# Rocketometer2148_MPU9150.net
KiCad netlist of a schematic drawn in EAGLE
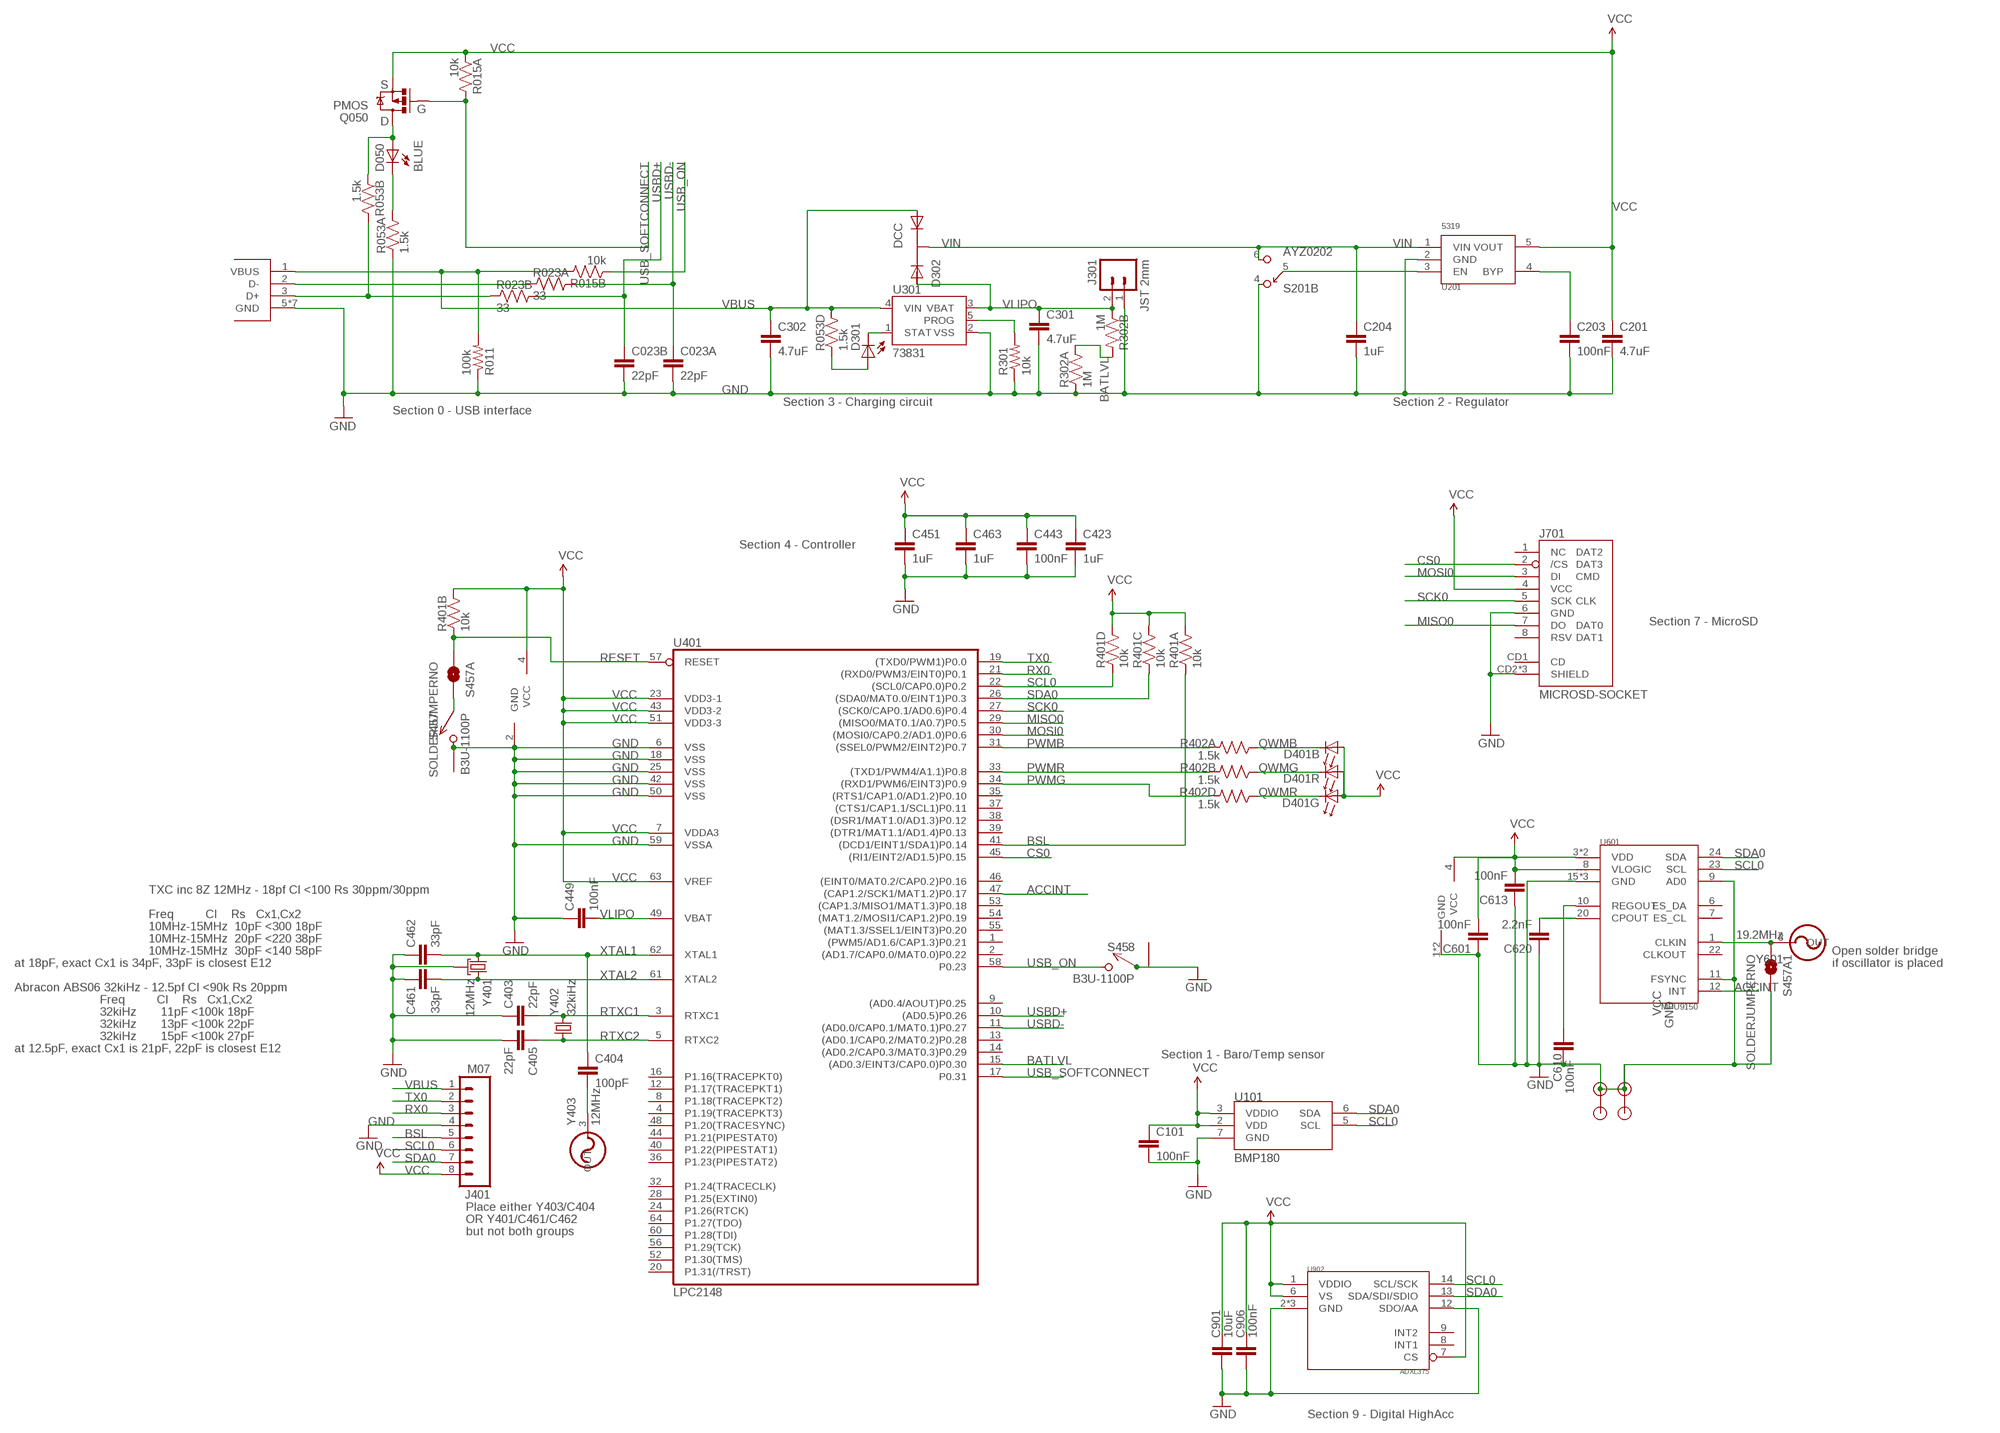
[diagram p0: schematic, sheet 1]

(export (version "E")
  (design (tool "Eeschema 10.0.6"))
  (components
    (comp (ref "C023")
      (value "22pF")
      (footprint "eagle-import:CKCM25")
      (fields (field (name "DIGIKEY") "445-1860-1-ND"))
      (libsource (lib "eagle-import") (part "CKCM25"))
    )
    (comp (ref "C101")
      (value "100nF")
      (footprint "eagle-import:0402-CAP")
      (libsource (lib "eagle-import") (part "CAP0402-CAP"))
    )
    (comp (ref "C201")
      (value "4.7uF")
      (footprint "eagle-import:0402-CAP")
      (libsource (lib "eagle-import") (part "CAP0402-CAP"))
    )
    (comp (ref "C203")
      (value "100nF")
      (footprint "eagle-import:0402-CAP")
      (libsource (lib "eagle-import") (part "CAP0402-CAP"))
    )
    (comp (ref "C204")
      (value "1uF")
      (footprint "eagle-import:0402-CAP")
      (libsource (lib "eagle-import") (part "CAP0402-CAP"))
    )
    (comp (ref "C301")
      (value "4.7uF")
      (footprint "eagle-import:0402-CAP")
      (libsource (lib "eagle-import") (part "CAP0402-CAP"))
    )
    (comp (ref "C302")
      (value "4.7uF")
      (footprint "eagle-import:0402-CAP")
      (libsource (lib "eagle-import") (part "CAP0402-CAP"))
    )
    (comp (ref "C403")
      (value "22pF")
      (footprint "eagle-import:0402-CAP")
      (libsource (lib "eagle-import") (part "CAP0402-CAP"))
    )
    (comp (ref "C404")
      (value "100pF")
      (footprint "eagle-import:0402-CAP")
      (libsource (lib "eagle-import") (part "CAP0402-CAP"))
    )
    (comp (ref "C405")
      (value "22pF")
      (footprint "eagle-import:0402-CAP")
      (libsource (lib "eagle-import") (part "CAP0402-CAP"))
    )
    (comp (ref "C423")
      (value "1uF")
      (footprint "eagle-import:0402-CAP")
      (libsource (lib "eagle-import") (part "CAP0402-CAP"))
    )
    (comp (ref "C443")
      (value "100nF")
      (footprint "eagle-import:0402-CAP")
      (libsource (lib "eagle-import") (part "CAP0402-CAP"))
    )
    (comp (ref "C449")
      (value "100nF")
      (footprint "eagle-import:0402-CAP")
      (libsource (lib "eagle-import") (part "CAP0402-CAP"))
    )
    (comp (ref "C451")
      (value "1uF")
      (footprint "eagle-import:0402-CAP")
      (libsource (lib "eagle-import") (part "CAP0402-CAP"))
    )
    (comp (ref "C461")
      (value "33pF")
      (footprint "eagle-import:0402-CAP")
      (libsource (lib "eagle-import") (part "CAP0402-CAP"))
    )
    (comp (ref "C462")
      (value "33pF")
      (footprint "eagle-import:0402-CAP")
      (libsource (lib "eagle-import") (part "CAP0402-CAP"))
    )
    (comp (ref "C463")
      (value "1uF")
      (footprint "eagle-import:0402-CAP")
      (libsource (lib "eagle-import") (part "CAP0402-CAP"))
    )
    (comp (ref "C601")
      (value "100nF")
      (footprint "eagle-import:0402-CAP")
      (libsource (lib "eagle-import") (part "CAP0402-CAP"))
    )
    (comp (ref "C610")
      (value "100nF")
      (footprint "eagle-import:0402-CAP")
      (libsource (lib "eagle-import") (part "CAP0402-CAP"))
    )
    (comp (ref "C613")
      (value "100nF")
      (footprint "eagle-import:0402-CAP")
      (libsource (lib "eagle-import") (part "CAP0402-CAP"))
    )
    (comp (ref "C620")
      (value "2.2nF")
      (footprint "eagle-import:0402-CAP")
      (libsource (lib "eagle-import") (part "CAP0402-CAP"))
    )
    (comp (ref "C901")
      (value "10uF")
      (footprint "eagle-import:0603-CAP")
      (libsource (lib "eagle-import") (part "CAP0603-CAP"))
    )
    (comp (ref "C906")
      (value "100nF")
      (footprint "eagle-import:0402-CAP")
      (libsource (lib "eagle-import") (part "SparkFun-Passives_CAP0402-CAP"))
    )
    (comp (ref "D050")
      (value "BLUE")
      (footprint "eagle-import:LED-0603")
      (libsource (lib "eagle-import") (part "LED0603"))
    )
    (comp (ref "D301")
      (value "YELLOW")
      (footprint "eagle-import:LED-0603")
      (libsource (lib "eagle-import") (part "LED0603"))
    )
    (comp (ref "D302")
      (value "DCC")
      (footprint "eagle-import:SOT-23-3")
      (libsource (lib "eagle-import") (part "PMEG2005CT"))
    )
    (comp (ref "D401")
      (value "SMLP36RGB2W(R)")
      (footprint "eagle-import:SMLP36")
      (fields (field (name "DIGIKEY") "846-1097-1-ND"))
      (libsource (lib "eagle-import") (part "SMLP36RGB2W(R)"))
    )
    (comp (ref "J001")
      (value "USB_MICROB_JSTGCT")
      (footprint "eagle-import:USB_MICROB_3075")
      (libsource (lib "eagle-import") (part "USB_MICROB_JSTGCT"))
    )
    (comp (ref "J301")
      (value "JST 2mm")
      (footprint "eagle-import:JST-2-SMD")
      (libsource (lib "eagle-import") (part "M02-JST-2MM-SMT"))
    )
    (comp (ref "J401")
      (value "M07")
      (footprint "eagle-import:1X08")
      (libsource (lib "eagle-import") (part "M081X08"))
    )
    (comp (ref "J701")
      (value "MICROSD-SOCKET")
      (footprint "eagle-import:MICROSD-SOCKET-PP")
      (libsource (lib "eagle-import") (part "MICROSD-SOCKET"))
    )
    (comp (ref "JP1")
      (value "STANDOFF")
      (footprint "eagle-import:STANDOFF")
      (libsource (lib "eagle-import") (part "STANDOFF"))
    )
    (comp (ref "JP2")
      (value "STANDOFF")
      (footprint "eagle-import:STANDOFF")
      (libsource (lib "eagle-import") (part "STANDOFF"))
    )
    (comp (ref "JP4")
      (value "STANDOFF")
      (footprint "eagle-import:STANDOFF")
      (libsource (lib "eagle-import") (part "STANDOFF"))
    )
    (comp (ref "JP5")
      (value "STANDOFF")
      (footprint "eagle-import:STANDOFF")
      (libsource (lib "eagle-import") (part "STANDOFF"))
    )
    (comp (ref "Q050")
      (value "PMOS")
      (footprint "eagle-import:SOT23-3")
      (libsource (lib "eagle-import") (part "MOSFET-PCHANNELSMD"))
    )
    (comp (ref "R011")
      (value "100k")
      (footprint "eagle-import:0402-RES")
      (libsource (lib "eagle-import") (part "RESISTOR0402-RES"))
    )
    (comp (ref "R015")
      (value "10k")
      (footprint "eagle-import:CRA02")
      (fields (field (name "DIGIKEY") "Y5103CT-ND"))
      (libsource (lib "eagle-import") (part "RP2EXB24V"))
    )
    (comp (ref "R023")
      (value "33")
      (footprint "eagle-import:CRA02")
      (libsource (lib "eagle-import") (part "RP2EXB24V"))
    )
    (comp (ref "R053")
      (value "1.5k")
      (footprint "eagle-import:CRA04")
      (fields (field (name "DIGIKEY") "CRA4S81.5KCT-ND"))
      (libsource (lib "eagle-import") (part "RP404"))
    )
    (comp (ref "R301")
      (value "10k")
      (footprint "eagle-import:0402-RES")
      (libsource (lib "eagle-import") (part "RESISTOR0402-RES"))
    )
    (comp (ref "R302")
      (value "1M")
      (footprint "eagle-import:CRA02")
      (libsource (lib "eagle-import") (part "RP2EXB24V"))
    )
    (comp (ref "R401")
      (value "10k")
      (footprint "eagle-import:CRA04")
      (fields (field (name "DIGIKEY") "CRA4S810KCT-ND"))
      (libsource (lib "eagle-import") (part "RP404"))
    )
    (comp (ref "R402")
      (value "1.5k")
      (footprint "eagle-import:CRA04")
      (fields (field (name "DIGIKEY") "CRA4S81.5KCT-ND"))
      (libsource (lib "eagle-import") (part "RP404"))
    )
    (comp (ref "S201")
      (value "AYZ0202")
      (footprint "eagle-import:AYZ0202")
      (libsource (lib "eagle-import") (part "AYZ0202"))
    )
    (comp (ref "S457")
      (value "B3U-1100P")
      (footprint "eagle-import:B3U-1100P")
      (fields (field (name "DIGIKEY") "SW1021CT-ND"))
      (libsource (lib "eagle-import") (part "B3U-1100P"))
    )
    (comp (ref "S457A")
      (value "SOLDERJUMPERNO")
      (footprint "eagle-import:SJ_2S-NO")
      (libsource (lib "eagle-import") (part "SOLDERJUMPERNO"))
    )
    (comp (ref "S457A1")
      (value "SOLDERJUMPERNO")
      (footprint "eagle-import:SJ_2S-NO")
      (libsource (lib "eagle-import") (part "SOLDERJUMPERNO"))
    )
    (comp (ref "S458")
      (value "B3U-1100P")
      (footprint "eagle-import:B3U-1100P")
      (fields (field (name "DIGIKEY") "SW1021CT-ND"))
      (libsource (lib "eagle-import") (part "B3U-1100P"))
    )
    (comp (ref "U101")
      (value "BMP180")
      (footprint "eagle-import:BMP180")
      (libsource (lib "eagle-import") (part "BMP180"))
    )
    (comp (ref "U201")
      (value "5319")
      (footprint "eagle-import:SOT-23-5")
      (libsource (lib "eagle-import") (part "MIC5319D5"))
    )
    (comp (ref "U301")
      (value "73831")
      (footprint "eagle-import:SOT23-5")
      (libsource (lib "eagle-import") (part "MCP73831"))
    )
    (comp (ref "U401")
      (value "LPC2148")
      (footprint "eagle-import:SQFP-S-10X10-64")
      (libsource (lib "eagle-import") (part "LPC213X"))
    )
    (comp (ref "U601")
      (value "MPU9150")
      (footprint "eagle-import:LLGA24")
      (libsource (lib "eagle-import") (part "MPU9150"))
    )
    (comp (ref "U902")
      (value "ADXL375")
      (footprint "eagle-import:ADXL375")
      (libsource (lib "eagle-import") (part "ADXL375"))
    )
    (comp (ref "Y401")
      (value "12MHz")
      (footprint "eagle-import:CRYSTAL_SMD_2MM_2_5MM")
      (libsource (lib "eagle-import") (part "CX2520"))
    )
    (comp (ref "Y402")
      (value "32kiHz")
      (footprint "eagle-import:ABS06")
      (libsource (lib "eagle-import") (part "ABS06"))
    )
    (comp (ref "Y403")
      (value "12MHz")
      (footprint "eagle-import:CRYSTAL_SMD_5MM_3_2MM")
      (fields (field (name "DIGIKEY") "631-1068-1-ND"))
      (libsource (lib "eagle-import") (part "OSCILLATORE35MT"))
    )
    (comp (ref "Y601")
      (value "19.2MHz")
      (footprint "eagle-import:CRYSTAL_SMD_2MM_2_5MM")
      (libsource (lib "eagle-import") (part "OSCILLATORASDMB"))
    )
  )
  (nets
    (net (code "1") (name "/ACCINT") (class "Default")
      (node (ref "U401") (pin "47") (pinfunction "(CAP1.2/SCK1/MAT1.2)P0.17_47") (pintype "bidirectional"))
      (node (ref "U601") (pin "12") (pinfunction "INT_12") (pintype "bidirectional"))
    )
    (net (code "2") (name "/BATLVL") (class "Default")
      (node (ref "R302") (pin "3") (pinfunction "2_3") (pintype "passive"))
      (node (ref "R302") (pin "4") (pinfunction "2_4") (pintype "passive"))
      (node (ref "U401") (pin "15") (pinfunction "(AD0.3/EINT3/CAP0.0)P0.30_15") (pintype "bidirectional"))
    )
    (net (code "3") (name "/BSL") (class "Default")
      (node (ref "J401") (pin "5") (pinfunction "5_5") (pintype "passive"))
      (node (ref "R401") (pin "1") (pinfunction "1_1") (pintype "passive"))
      (node (ref "U401") (pin "41") (pinfunction "(DCD1/EINT1/SDA1)P0.14_41") (pintype "bidirectional"))
    )
    (net (code "4") (name "/CS0") (class "Default")
      (node (ref "J701") (pin "2") (pinfunction "/CS_2") (pintype "bidirectional"))
      (node (ref "U401") (pin "45") (pinfunction "(RI1/EINT2/AD1.5)P0.15_45") (pintype "bidirectional"))
    )
    (net (code "5") (name "/MISO0") (class "Default")
      (node (ref "J701") (pin "7") (pinfunction "DO_7") (pintype "bidirectional"))
      (node (ref "U401") (pin "29") (pinfunction "(MISO0/MAT0.1/A0.7)P0.5_29") (pintype "bidirectional"))
    )
    (net (code "6") (name "/MOSI0") (class "Default")
      (node (ref "J701") (pin "3") (pinfunction "DI_3") (pintype "bidirectional"))
      (node (ref "U401") (pin "30") (pinfunction "(MOSI0/CAP0.2/AD1.0)P0.6_30") (pintype "bidirectional"))
    )
    (net (code "7") (name "/PWMB") (class "Default")
      (node (ref "R402") (pin "8") (pinfunction "2_8") (pintype "passive"))
      (node (ref "U401") (pin "31") (pinfunction "(SSEL0/PWM2/EINT2)P0.7_31") (pintype "bidirectional"))
    )
    (net (code "8") (name "/PWMG") (class "Default")
      (node (ref "R402") (pin "5") (pinfunction "2_5") (pintype "passive"))
      (node (ref "U401") (pin "34") (pinfunction "(RXD1/PWM6/EINT3)P0.9_34") (pintype "bidirectional"))
    )
    (net (code "9") (name "/PWMR") (class "Default")
      (node (ref "R402") (pin "7") (pinfunction "2_7") (pintype "passive"))
      (node (ref "U401") (pin "33") (pinfunction "(TXD1/PWM4/A1.1)P0.8_33") (pintype "bidirectional"))
    )
    (net (code "10") (name "/QWMB") (class "Default")
      (node (ref "D401") (pin "1") (pinfunction "C_1") (pintype "passive"))
      (node (ref "R402") (pin "1") (pinfunction "1_1") (pintype "passive"))
    )
    (net (code "11") (name "/QWMG") (class "Default")
      (node (ref "D401") (pin "5") (pinfunction "C_5") (pintype "passive"))
      (node (ref "R402") (pin "4") (pinfunction "1_4") (pintype "passive"))
    )
    (net (code "12") (name "/QWMR") (class "Default")
      (node (ref "D401") (pin "3") (pinfunction "C_3") (pintype "passive"))
      (node (ref "R402") (pin "2") (pinfunction "1_2") (pintype "passive"))
    )
    (net (code "13") (name "/RESET") (class "Default")
      (node (ref "R401") (pin "2") (pinfunction "1_2") (pintype "passive"))
      (node (ref "S457A") (pin "1") (pinfunction "1_1") (pintype "passive"))
      (node (ref "U401") (pin "57") (pinfunction "RESET_57") (pintype "input"))
    )
    (net (code "14") (name "/RTXC1") (class "Default")
      (node (ref "C403") (pin "2") (pinfunction "2_2") (pintype "passive"))
      (node (ref "U401") (pin "3") (pinfunction "RTXC1_3") (pintype "input"))
      (node (ref "Y402") (pin "2") (pinfunction "2_2") (pintype "passive"))
    )
    (net (code "15") (name "/RTXC2") (class "Default")
      (node (ref "C405") (pin "1") (pinfunction "1_1") (pintype "passive"))
      (node (ref "U401") (pin "5") (pinfunction "RTXC2_5") (pintype "output"))
      (node (ref "Y402") (pin "1") (pinfunction "1_1") (pintype "passive"))
    )
    (net (code "16") (name "/RX0") (class "Default")
      (node (ref "J401") (pin "3") (pinfunction "3_3") (pintype "passive"))
      (node (ref "U401") (pin "21") (pinfunction "(RXD0/PWM3/EINT0)P0.1_21") (pintype "bidirectional"))
    )
    (net (code "17") (name "/SCK0") (class "Default")
      (node (ref "J701") (pin "5") (pinfunction "SCK_5") (pintype "bidirectional"))
      (node (ref "U401") (pin "27") (pinfunction "(SCK0/CAP0.1/AD0.6)P0.4_27") (pintype "bidirectional"))
    )
    (net (code "18") (name "/SCL0") (class "Default")
      (node (ref "J401") (pin "6") (pinfunction "6_6") (pintype "passive"))
      (node (ref "R401") (pin "4") (pinfunction "1_4") (pintype "passive"))
      (node (ref "U101") (pin "5") (pinfunction "SCL_5") (pintype "input"))
      (node (ref "U401") (pin "22") (pinfunction "(SCL0/CAP0.0)P0.2_22") (pintype "bidirectional"))
      (node (ref "U601") (pin "23") (pinfunction "SCL_23") (pintype "bidirectional"))
      (node (ref "U902") (pin "14") (pinfunction "SCL/SCK_14") (pintype "input"))
    )
    (net (code "19") (name "/SDA0") (class "Default")
      (node (ref "J401") (pin "7") (pinfunction "7_7") (pintype "passive"))
      (node (ref "R401") (pin "3") (pinfunction "1_3") (pintype "passive"))
      (node (ref "U101") (pin "6") (pinfunction "SDA_6") (pintype "bidirectional"))
      (node (ref "U401") (pin "26") (pinfunction "(SDA0/MAT0.0/EINT1)P0.3_26") (pintype "bidirectional"))
      (node (ref "U601") (pin "24") (pinfunction "SDA_24") (pintype "bidirectional"))
      (node (ref "U902") (pin "13") (pinfunction "SDA/SDI/SDIO_13") (pintype "bidirectional"))
    )
    (net (code "20") (name "/TX0") (class "Default")
      (node (ref "J401") (pin "2") (pinfunction "2_2") (pintype "passive"))
      (node (ref "U401") (pin "19") (pinfunction "(TXD0/PWM1)P0.0_19") (pintype "bidirectional"))
    )
    (net (code "21") (name "/USBD+") (class "Default")
      (node (ref "C023") (pin "2") (pinfunction "1_2") (pintype "passive"))
      (node (ref "R023") (pin "3") (pinfunction "2_3") (pintype "passive"))
      (node (ref "U401") (pin "10") (pinfunction "(AD0.5)P0.26_10") (pintype "bidirectional"))
    )
    (net (code "22") (name "/USBD-") (class "Default")
      (node (ref "C023") (pin "1") (pinfunction "1_1") (pintype "passive"))
      (node (ref "R023") (pin "4") (pinfunction "2_4") (pintype "passive"))
      (node (ref "U401") (pin "11") (pinfunction "(AD0.0/CAP0.1/MAT0.1)P0.27_11") (pintype "bidirectional"))
    )
    (net (code "23") (name "/USB_ON") (class "Default")
      (node (ref "R015") (pin "2") (pinfunction "1_2") (pintype "passive"))
      (node (ref "S458") (pin "P$2") (pinfunction "2_P$2") (pintype "bidirectional"))
      (node (ref "U401") (pin "58") (pinfunction "P0.23_58") (pintype "bidirectional"))
    )
    (net (code "24") (name "/USB_SOFTCONNECT") (class "Default")
      (node (ref "Q050") (pin "1") (pinfunction "G_1") (pintype "passive"))
      (node (ref "R015") (pin "4") (pinfunction "2_4") (pintype "passive"))
      (node (ref "U401") (pin "17") (pinfunction "P0.31_17") (pintype "output"))
    )
    (net (code "25") (name "/VBUS") (class "Default")
      (node (ref "C302") (pin "1") (pinfunction "1_1") (pintype "passive"))
      (node (ref "D302") (pin "1") (pinfunction "A1_1") (pintype "passive"))
      (node (ref "J001") (pin "1") (pinfunction "VBUS_1") (pintype "bidirectional"))
      (node (ref "J401") (pin "1") (pinfunction "1_1") (pintype "passive"))
      (node (ref "R011") (pin "2") (pinfunction "2_2") (pintype "passive"))
      (node (ref "R015") (pin "3") (pinfunction "2_3") (pintype "passive"))
      (node (ref "R053") (pin "5") (pinfunction "2_5") (pintype "passive"))
      (node (ref "U301") (pin "4") (pinfunction "VIN_4") (pintype "power_in"))
    )
    (net (code "26") (name "/VIN") (class "Default")
      (node (ref "C204") (pin "1") (pinfunction "1_1") (pintype "passive"))
      (node (ref "D302") (pin "3") (pinfunction "K_3") (pintype "passive"))
      (node (ref "S201") (pin "6") (pinfunction "P$2_6") (pintype "bidirectional"))
      (node (ref "U201") (pin "1") (pinfunction "VIN_1") (pintype "bidirectional"))
    )
    (net (code "27") (name "/VLIPO") (class "Default")
      (node (ref "C301") (pin "1") (pinfunction "1_1") (pintype "passive"))
      (node (ref "C449") (pin "2") (pinfunction "2_2") (pintype "passive"))
      (node (ref "D302") (pin "2") (pinfunction "A2_2") (pintype "passive"))
      (node (ref "J301") (pin "2") (pinfunction "2_2") (pintype "passive"))
      (node (ref "R302") (pin "2") (pinfunction "1_2") (pintype "passive"))
      (node (ref "U301") (pin "3") (pinfunction "VBAT_3") (pintype "power_in"))
      (node (ref "U401") (pin "49") (pinfunction "VBAT_49") (pintype "power_in"))
    )
    (net (code "28") (name "/XTAL1") (class "Default")
      (node (ref "C404") (pin "1") (pinfunction "1_1") (pintype "passive"))
      (node (ref "C462") (pin "2") (pinfunction "2_2") (pintype "passive"))
      (node (ref "U401") (pin "62") (pinfunction "XTAL1_62") (pintype "input"))
      (node (ref "Y401") (pin "1") (pinfunction "1_1") (pintype "passive"))
    )
    (net (code "29") (name "/XTAL2") (class "Default")
      (node (ref "C461") (pin "2") (pinfunction "2_2") (pintype "passive"))
      (node (ref "U401") (pin "61") (pinfunction "XTAL2_61") (pintype "output"))
      (node (ref "Y401") (pin "3") (pinfunction "2_3") (pintype "passive"))
    )
    (net (code "30") (name "GND") (class "Default")
      (node (ref "C023") (pin "3") (pinfunction "2_3") (pintype "passive"))
      (node (ref "C023") (pin "4") (pinfunction "2_4") (pintype "passive"))
      (node (ref "C101") (pin "2") (pinfunction "2_2") (pintype "passive"))
      (node (ref "C201") (pin "2") (pinfunction "2_2") (pintype "passive"))
      (node (ref "C203") (pin "2") (pinfunction "2_2") (pintype "passive"))
      (node (ref "C204") (pin "2") (pinfunction "2_2") (pintype "passive"))
      (node (ref "C301") (pin "2") (pinfunction "2_2") (pintype "passive"))
      (node (ref "C302") (pin "2") (pinfunction "2_2") (pintype "passive"))
      (node (ref "C403") (pin "1") (pinfunction "1_1") (pintype "passive"))
      (node (ref "C405") (pin "2") (pinfunction "2_2") (pintype "passive"))
      (node (ref "C423") (pin "2") (pinfunction "2_2") (pintype "passive"))
      (node (ref "C443") (pin "2") (pinfunction "2_2") (pintype "passive"))
      (node (ref "C449") (pin "1") (pinfunction "1_1") (pintype "passive"))
      (node (ref "C451") (pin "2") (pinfunction "2_2") (pintype "passive"))
      (node (ref "C461") (pin "1") (pinfunction "1_1") (pintype "passive"))
      (node (ref "C462") (pin "1") (pinfunction "1_1") (pintype "passive"))
      (node (ref "C463") (pin "2") (pinfunction "2_2") (pintype "passive"))
      (node (ref "C601") (pin "1") (pinfunction "1_1") (pintype "passive"))
      (node (ref "C610") (pin "2") (pinfunction "2_2") (pintype "passive"))
      (node (ref "C613") (pin "1") (pinfunction "1_1") (pintype "passive"))
      (node (ref "C620") (pin "1") (pinfunction "1_1") (pintype "passive"))
      (node (ref "C901") (pin "2") (pinfunction "2_2") (pintype "passive"))
      (node (ref "C906") (pin "2") (pinfunction "2_2") (pintype "passive"))
      (node (ref "J001") (pin "5") (pinfunction "GND_5") (pintype "bidirectional"))
      (node (ref "J001") (pin "P$1") (pinfunction "GND_P$1") (pintype "bidirectional"))
      (node (ref "J001") (pin "P$10") (pinfunction "GND_P$10") (pintype "bidirectional"))
      (node (ref "J001") (pin "P$2") (pinfunction "GND_P$2") (pintype "bidirectional"))
      (node (ref "J001") (pin "P$3") (pinfunction "GND_P$3") (pintype "bidirectional"))
      (node (ref "J001") (pin "P$4") (pinfunction "GND_P$4") (pintype "bidirectional"))
      (node (ref "J001") (pin "P$8") (pinfunction "GND_P$8") (pintype "bidirectional"))
      (node (ref "J301") (pin "1") (pinfunction "1_1") (pintype "passive"))
      (node (ref "J401") (pin "4") (pinfunction "4_4") (pintype "passive"))
      (node (ref "J701") (pin "6") (pinfunction "GND_6") (pintype "bidirectional"))
      (node (ref "J701") (pin "CD2") (pinfunction "SHIELD_CD2") (pintype "bidirectional"))
      (node (ref "J701") (pin "GND1") (pinfunction "SHIELD_GND1") (pintype "bidirectional"))
      (node (ref "J701") (pin "GND3") (pinfunction "SHIELD_GND3") (pintype "bidirectional"))
      (node (ref "JP1") (pin "P$1") (pinfunction "P$1_P$1") (pintype "bidirectional"))
      (node (ref "JP2") (pin "P$1") (pinfunction "P$1_P$1") (pintype "bidirectional"))
      (node (ref "JP4") (pin "P$1") (pinfunction "P$1_P$1") (pintype "bidirectional"))
      (node (ref "JP5") (pin "P$1") (pinfunction "P$1_P$1") (pintype "bidirectional"))
      (node (ref "R011") (pin "1") (pinfunction "1_1") (pintype "passive"))
      (node (ref "R053") (pin "1") (pinfunction "1_1") (pintype "passive"))
      (node (ref "R301") (pin "1") (pinfunction "1_1") (pintype "passive"))
      (node (ref "R302") (pin "1") (pinfunction "1_1") (pintype "passive"))
      (node (ref "S201") (pin "4") (pinfunction "P$1_4") (pintype "bidirectional"))
      (node (ref "S457") (pin "P$2") (pinfunction "2_P$2") (pintype "bidirectional"))
      (node (ref "S457") (pin "P$3") (pinfunction "1_P$3") (pintype "bidirectional"))
      (node (ref "S457A1") (pin "2") (pinfunction "2_2") (pintype "passive"))
      (node (ref "S458") (pin "P$1") (pinfunction "1_P$1") (pintype "bidirectional"))
      (node (ref "S458") (pin "P$3") (pinfunction "1_P$3") (pintype "bidirectional"))
      (node (ref "U101") (pin "7") (pinfunction "GND_7") (pintype "power_in"))
      (node (ref "U201") (pin "2") (pinfunction "GND_2") (pintype "bidirectional"))
      (node (ref "U301") (pin "2") (pinfunction "VSS_2") (pintype "power_in"))
      (node (ref "U401") (pin "18") (pinfunction "VSS_18") (pintype "power_in"))
      (node (ref "U401") (pin "25") (pinfunction "VSS_25") (pintype "power_in"))
      (node (ref "U401") (pin "42") (pinfunction "VSS_42") (pintype "power_in"))
      (node (ref "U401") (pin "50") (pinfunction "VSS_50") (pintype "power_in"))
      (node (ref "U401") (pin "59") (pinfunction "VSSA_59") (pintype "power_in"))
      (node (ref "U401") (pin "6") (pinfunction "VSS_6") (pintype "power_in"))
      (node (ref "U601") (pin "11") (pinfunction "FSYNC_11") (pintype "bidirectional"))
      (node (ref "U601") (pin "15") (pinfunction "GND_15") (pintype "bidirectional"))
      (node (ref "U601") (pin "17") (pinfunction "GND_17") (pintype "bidirectional"))
      (node (ref "U601") (pin "18") (pinfunction "GND_18") (pintype "bidirectional"))
      (node (ref "U601") (pin "9") (pinfunction "AD0_9") (pintype "bidirectional"))
      (node (ref "U902") (pin "12") (pinfunction "SDO/AA_12") (pintype "bidirectional"))
      (node (ref "U902") (pin "2") (pinfunction "GND_2") (pintype "power_in"))
      (node (ref "U902") (pin "4") (pinfunction "GND_4") (pintype "power_in"))
      (node (ref "U902") (pin "5") (pinfunction "GND_5") (pintype "power_in"))
      (node (ref "Y401") (pin "2") (pinfunction "GND_2") (pintype "passive"))
      (node (ref "Y401") (pin "4") (pinfunction "GND_4") (pintype "passive"))
      (node (ref "Y403") (pin "2") (pinfunction "GND_2") (pintype "bidirectional"))
      (node (ref "Y601") (pin "1") (pinfunction "GND_1") (pintype "bidirectional"))
      (node (ref "Y601") (pin "2") (pinfunction "GND_2") (pintype "bidirectional"))
    )
    (net (code "31") (name "Net-(J001-D+)") (class "Default")
      (node (ref "J001") (pin "3") (pinfunction "D+_3") (pintype "bidirectional"))
      (node (ref "R023") (pin "2") (pinfunction "1_2") (pintype "passive"))
      (node (ref "R053") (pin "7") (pinfunction "2_7") (pintype "passive"))
    )
    (net (code "32") (name "Net-(J001-D-)") (class "Default")
      (node (ref "J001") (pin "2") (pinfunction "D-_2") (pintype "bidirectional"))
      (node (ref "R023") (pin "1") (pinfunction "1_1") (pintype "passive"))
    )
    (net (code "33") (name "Net-(Q050-D)") (class "Default")
      (node (ref "D050") (pin "A") (pinfunction "A_A") (pintype "passive"))
      (node (ref "Q050") (pin "3") (pinfunction "D_3") (pintype "passive"))
      (node (ref "R053") (pin "2") (pinfunction "1_2") (pintype "passive"))
    )
    (net (code "34") (name "Net-(R053A-2)") (class "Default")
      (node (ref "D050") (pin "C") (pinfunction "C_C") (pintype "passive"))
      (node (ref "R053") (pin "8") (pinfunction "2_8") (pintype "passive"))
    )
    (net (code "35") (name "Net-(R053D-1)") (class "Default")
      (node (ref "D301") (pin "A") (pinfunction "A_A") (pintype "passive"))
      (node (ref "R053") (pin "4") (pinfunction "1_4") (pintype "passive"))
    )
    (net (code "36") (name "Net-(S201B-P$3)") (class "Default")
      (node (ref "S201") (pin "5") (pinfunction "P$3_5") (pintype "bidirectional"))
      (node (ref "U201") (pin "3") (pinfunction "EN_3") (pintype "bidirectional"))
    )
    (net (code "37") (name "Net-(S457B-1)") (class "Default")
      (node (ref "S457") (pin "P$1") (pinfunction "1_P$1") (pintype "bidirectional"))
      (node (ref "S457A") (pin "2") (pinfunction "2_2") (pintype "passive"))
    )
    (net (code "38") (name "Net-(U201-BYP)") (class "Default")
      (node (ref "C203") (pin "1") (pinfunction "1_1") (pintype "passive"))
      (node (ref "U201") (pin "4") (pinfunction "BYP_4") (pintype "bidirectional"))
    )
    (net (code "39") (name "Net-(U301-PROG)") (class "Default")
      (node (ref "R301") (pin "2") (pinfunction "2_2") (pintype "passive"))
      (node (ref "U301") (pin "5") (pinfunction "PROG_5") (pintype "input"))
    )
    (net (code "40") (name "Net-(U301-STAT)") (class "Default")
      (node (ref "D301") (pin "C") (pinfunction "C_C") (pintype "passive"))
      (node (ref "U301") (pin "1") (pinfunction "STAT_1") (pintype "output"))
    )
    (net (code "41") (name "Net-(U601-CLKIN)") (class "Default")
      (node (ref "S457A1") (pin "1") (pinfunction "1_1") (pintype "passive"))
      (node (ref "U601") (pin "1") (pinfunction "CLKIN_1") (pintype "bidirectional"))
      (node (ref "Y601") (pin "3") (pinfunction "OUT_3") (pintype "bidirectional"))
    )
    (net (code "42") (name "Net-(U601-CPOUT)") (class "Default")
      (node (ref "C620") (pin "2") (pinfunction "2_2") (pintype "passive"))
      (node (ref "U601") (pin "20") (pinfunction "CPOUT_20") (pintype "bidirectional"))
    )
    (net (code "43") (name "Net-(U601-REGOUT)") (class "Default")
      (node (ref "C610") (pin "1") (pinfunction "1_1") (pintype "passive"))
      (node (ref "U601") (pin "10") (pinfunction "REGOUT_10") (pintype "bidirectional"))
    )
    (net (code "44") (name "Net-(Y403A-OUT)") (class "Default")
      (node (ref "C404") (pin "2") (pinfunction "2_2") (pintype "passive"))
      (node (ref "Y403") (pin "3") (pinfunction "OUT_3") (pintype "bidirectional"))
    )
    (net (code "45") (name "VCC") (class "Default")
      (node (ref "C101") (pin "1") (pinfunction "1_1") (pintype "passive"))
      (node (ref "C201") (pin "1") (pinfunction "1_1") (pintype "passive"))
      (node (ref "C423") (pin "1") (pinfunction "1_1") (pintype "passive"))
      (node (ref "C443") (pin "1") (pinfunction "1_1") (pintype "passive"))
      (node (ref "C451") (pin "1") (pinfunction "1_1") (pintype "passive"))
      (node (ref "C463") (pin "1") (pinfunction "1_1") (pintype "passive"))
      (node (ref "C601") (pin "2") (pinfunction "2_2") (pintype "passive"))
      (node (ref "C613") (pin "2") (pinfunction "2_2") (pintype "passive"))
      (node (ref "C901") (pin "1") (pinfunction "1_1") (pintype "passive"))
      (node (ref "C906") (pin "1") (pinfunction "1_1") (pintype "passive"))
      (node (ref "D401") (pin "2") (pinfunction "A_2") (pintype "passive"))
      (node (ref "D401") (pin "4") (pinfunction "A_4") (pintype "passive"))
      (node (ref "D401") (pin "6") (pinfunction "A_6") (pintype "passive"))
      (node (ref "J401") (pin "8") (pinfunction "8_8") (pintype "passive"))
      (node (ref "J701") (pin "4") (pinfunction "VCC_4") (pintype "bidirectional"))
      (node (ref "Q050") (pin "2") (pinfunction "S_2") (pintype "passive"))
      (node (ref "R015") (pin "1") (pinfunction "1_1") (pintype "passive"))
      (node (ref "R401") (pin "5") (pinfunction "2_5") (pintype "passive"))
      (node (ref "R401") (pin "6") (pinfunction "2_6") (pintype "passive"))
      (node (ref "R401") (pin "7") (pinfunction "2_7") (pintype "passive"))
      (node (ref "R401") (pin "8") (pinfunction "2_8") (pintype "passive"))
      (node (ref "U101") (pin "2") (pinfunction "VDD_2") (pintype "power_in"))
      (node (ref "U101") (pin "3") (pinfunction "VDDIO_3") (pintype "power_in"))
      (node (ref "U201") (pin "5") (pinfunction "VOUT_5") (pintype "bidirectional"))
      (node (ref "U401") (pin "23") (pinfunction "VDD3-1_23") (pintype "power_in"))
      (node (ref "U401") (pin "43") (pinfunction "VDD3-2_43") (pintype "power_in"))
      (node (ref "U401") (pin "51") (pinfunction "VDD3-3_51") (pintype "power_in"))
      (node (ref "U401") (pin "63") (pinfunction "VREF_63") (pintype "input"))
      (node (ref "U401") (pin "7") (pinfunction "VDDA3_7") (pintype "power_in"))
      (node (ref "U601") (pin "13") (pinfunction "VDD_13") (pintype "bidirectional"))
      (node (ref "U601") (pin "3") (pinfunction "VDD_3") (pintype "bidirectional"))
      (node (ref "U601") (pin "8") (pinfunction "VLOGIC_8") (pintype "bidirectional"))
      (node (ref "U902") (pin "1") (pinfunction "VDDIO_1") (pintype "power_in"))
      (node (ref "U902") (pin "6") (pinfunction "VS_6") (pintype "power_in"))
      (node (ref "U902") (pin "7") (pinfunction "CS_7") (pintype "input"))
      (node (ref "Y403") (pin "4") (pinfunction "VCC_4") (pintype "bidirectional"))
      (node (ref "Y601") (pin "4") (pinfunction "VCC_4") (pintype "bidirectional"))
    )
    (net (code "46") (name "unconnected-(J701-CD-PadCD1)") (class "Default")
      (node (ref "J701") (pin "CD1") (pinfunction "CD_CD1") (pintype "bidirectional"))
    )
    (net (code "47") (name "unconnected-(J701-NC-Pad1)") (class "Default")
      (node (ref "J701") (pin "1") (pinfunction "NC_1") (pintype "bidirectional"))
    )
    (net (code "48") (name "unconnected-(J701-RSV-Pad8)") (class "Default")
      (node (ref "J701") (pin "8") (pinfunction "RSV_8") (pintype "bidirectional"))
    )
    (net (code "49") (name "unconnected-(U401-(AD0.1{slash}CAP0.2{slash}MAT0.2)P0.28-Pad13)") (class "Default")
      (node (ref "U401") (pin "13") (pinfunction "(AD0.1/CAP0.2/MAT0.2)P0.28_13") (pintype "bidirectional"))
    )
    (net (code "50") (name "unconnected-(U401-(AD0.2{slash}CAP0.3{slash}MAT0.3)P0.29-Pad14)") (class "Default")
      (node (ref "U401") (pin "14") (pinfunction "(AD0.2/CAP0.3/MAT0.3)P0.29_14") (pintype "bidirectional"))
    )
    (net (code "51") (name "unconnected-(U401-(AD0.4{slash}AOUT)P0.25-Pad9)") (class "Default")
      (node (ref "U401") (pin "9") (pinfunction "(AD0.4/AOUT)P0.25_9") (pintype "bidirectional"))
    )
    (net (code "52") (name "unconnected-(U401-(AD1.7{slash}CAP0.0{slash}MAT0.0)P0.22-Pad2)") (class "Default")
      (node (ref "U401") (pin "2") (pinfunction "(AD1.7/CAP0.0/MAT0.0)P0.22_2") (pintype "bidirectional"))
    )
    (net (code "53") (name "unconnected-(U401-(CAP1.3{slash}MISO1{slash}MAT1.3)P0.18-Pad53)") (class "Default")
      (node (ref "U401") (pin "53") (pinfunction "(CAP1.3/MISO1/MAT1.3)P0.18_53") (pintype "bidirectional"))
    )
    (net (code "54") (name "unconnected-(U401-(CTS1{slash}CAP1.1{slash}SCL1)P0.11-Pad37)") (class "Default")
      (node (ref "U401") (pin "37") (pinfunction "(CTS1/CAP1.1/SCL1)P0.11_37") (pintype "bidirectional"))
    )
    (net (code "55") (name "unconnected-(U401-(DSR1{slash}MAT1.0{slash}AD1.3)P0.12-Pad38)") (class "Default")
      (node (ref "U401") (pin "38") (pinfunction "(DSR1/MAT1.0/AD1.3)P0.12_38") (pintype "bidirectional"))
    )
    (net (code "56") (name "unconnected-(U401-(DTR1{slash}MAT1.1{slash}AD1.4)P0.13-Pad39)") (class "Default")
      (node (ref "U401") (pin "39") (pinfunction "(DTR1/MAT1.1/AD1.4)P0.13_39") (pintype "bidirectional"))
    )
    (net (code "57") (name "unconnected-(U401-(EINT0{slash}MAT0.2{slash}CAP0.2)P0.16-Pad46)") (class "Default")
      (node (ref "U401") (pin "46") (pinfunction "(EINT0/MAT0.2/CAP0.2)P0.16_46") (pintype "bidirectional"))
    )
    (net (code "58") (name "unconnected-(U401-(MAT1.2{slash}MOSI1{slash}CAP1.2)P0.19-Pad54)") (class "Default")
      (node (ref "U401") (pin "54") (pinfunction "(MAT1.2/MOSI1/CAP1.2)P0.19_54") (pintype "bidirectional"))
    )
    (net (code "59") (name "unconnected-(U401-(MAT1.3{slash}SSEL1{slash}EINT3)P0.20-Pad55)") (class "Default")
      (node (ref "U401") (pin "55") (pinfunction "(MAT1.3/SSEL1/EINT3)P0.20_55") (pintype "bidirectional"))
    )
    (net (code "60") (name "unconnected-(U401-(PWM5{slash}AD1.6{slash}CAP1.3)P0.21-Pad1)") (class "Default")
      (node (ref "U401") (pin "1") (pinfunction "(PWM5/AD1.6/CAP1.3)P0.21_1") (pintype "bidirectional"))
    )
    (net (code "61") (name "unconnected-(U401-(RTS1{slash}CAP1.0{slash}AD1.2)P0.10-Pad35)") (class "Default")
      (node (ref "U401") (pin "35") (pinfunction "(RTS1/CAP1.0/AD1.2)P0.10_35") (pintype "bidirectional"))
    )
    (net (code "62") (name "unconnected-(U401-P1.16(TRACEPKT0)-Pad16)") (class "Default")
      (node (ref "U401") (pin "16") (pinfunction "P1.16(TRACEPKT0)_16") (pintype "bidirectional"))
    )
    (net (code "63") (name "unconnected-(U401-P1.17(TRACEPKT1)-Pad12)") (class "Default")
      (node (ref "U401") (pin "12") (pinfunction "P1.17(TRACEPKT1)_12") (pintype "bidirectional"))
    )
    (net (code "64") (name "unconnected-(U401-P1.18(TRACEPKT2)-Pad8)") (class "Default")
      (node (ref "U401") (pin "8") (pinfunction "P1.18(TRACEPKT2)_8") (pintype "bidirectional"))
    )
    (net (code "65") (name "unconnected-(U401-P1.19(TRACEPKT3)-Pad4)") (class "Default")
      (node (ref "U401") (pin "4") (pinfunction "P1.19(TRACEPKT3)_4") (pintype "bidirectional"))
    )
    (net (code "66") (name "unconnected-(U401-P1.20(TRACESYNC)-Pad48)") (class "Default")
      (node (ref "U401") (pin "48") (pinfunction "P1.20(TRACESYNC)_48") (pintype "bidirectional"))
    )
    (net (code "67") (name "unconnected-(U401-P1.21(PIPESTAT0)-Pad44)") (class "Default")
      (node (ref "U401") (pin "44") (pinfunction "P1.21(PIPESTAT0)_44") (pintype "bidirectional"))
    )
    (net (code "68") (name "unconnected-(U401-P1.22(PIPESTAT1)-Pad40)") (class "Default")
      (node (ref "U401") (pin "40") (pinfunction "P1.22(PIPESTAT1)_40") (pintype "bidirectional"))
    )
    (net (code "69") (name "unconnected-(U401-P1.23(PIPESTAT2)-Pad36)") (class "Default")
      (node (ref "U401") (pin "36") (pinfunction "P1.23(PIPESTAT2)_36") (pintype "bidirectional"))
    )
    (net (code "70") (name "unconnected-(U401-P1.24(TRACECLK)-Pad32)") (class "Default")
      (node (ref "U401") (pin "32") (pinfunction "P1.24(TRACECLK)_32") (pintype "bidirectional"))
    )
    (net (code "71") (name "unconnected-(U401-P1.25(EXTIN0)-Pad28)") (class "Default")
      (node (ref "U401") (pin "28") (pinfunction "P1.25(EXTIN0)_28") (pintype "bidirectional"))
    )
    (net (code "72") (name "unconnected-(U401-P1.26(RTCK)-Pad24)") (class "Default")
      (node (ref "U401") (pin "24") (pinfunction "P1.26(RTCK)_24") (pintype "bidirectional"))
    )
    (net (code "73") (name "unconnected-(U401-P1.27(TDO)-Pad64)") (class "Default")
      (node (ref "U401") (pin "64") (pinfunction "P1.27(TDO)_64") (pintype "bidirectional"))
    )
    (net (code "74") (name "unconnected-(U401-P1.28(TDI)-Pad60)") (class "Default")
      (node (ref "U401") (pin "60") (pinfunction "P1.28(TDI)_60") (pintype "bidirectional"))
    )
    (net (code "75") (name "unconnected-(U401-P1.29(TCK)-Pad56)") (class "Default")
      (node (ref "U401") (pin "56") (pinfunction "P1.29(TCK)_56") (pintype "bidirectional"))
    )
    (net (code "76") (name "unconnected-(U401-P1.30(TMS)-Pad52)") (class "Default")
      (node (ref "U401") (pin "52") (pinfunction "P1.30(TMS)_52") (pintype "bidirectional"))
    )
    (net (code "77") (name "unconnected-(U401-P1.31({slash}TRST)-Pad20)") (class "Default")
      (node (ref "U401") (pin "20") (pinfunction "P1.31(/TRST)_20") (pintype "bidirectional"))
    )
    (net (code "78") (name "unconnected-(U601-CLKOUT-Pad22)") (class "Default")
      (node (ref "U601") (pin "22") (pinfunction "CLKOUT_22") (pintype "bidirectional"))
    )
    (net (code "79") (name "unconnected-(U601-ES_CL-Pad7)") (class "Default")
      (node (ref "U601") (pin "7") (pinfunction "ES_CL_7") (pintype "bidirectional"))
    )
    (net (code "80") (name "unconnected-(U601-ES_DA-Pad6)") (class "Default")
      (node (ref "U601") (pin "6") (pinfunction "ES_DA_6") (pintype "bidirectional"))
    )
    (net (code "81") (name "unconnected-(U902-INT1-Pad8)") (class "Default")
      (node (ref "U902") (pin "8") (pinfunction "INT1_8") (pintype "output"))
    )
    (net (code "82") (name "unconnected-(U902-INT2-Pad9)") (class "Default")
      (node (ref "U902") (pin "9") (pinfunction "INT2_9") (pintype "output"))
    )
  )
)
